# 3V3_LDO.net
KiCad netlist of a schematic drawn in Altium Designer
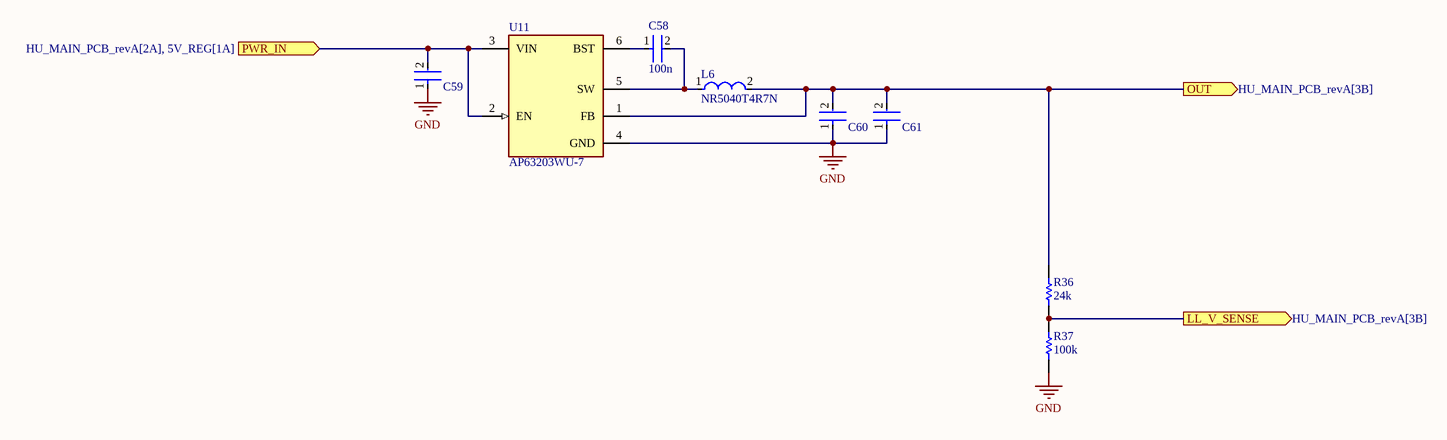
[diagram p0: 3V3_LDO.SchDoc]

(export (version "E")
  (design (tool "Eeschema 10.0.6"))
  (components
    (comp (ref "C58")
      (value "100n")
      (footprint "FP-0402-L_1_0_0_05-W_0_5-IPC_A")
      (description "LARGE PADS, 0402 CAP, CHANGE COMMENT TO MATCH REAL P/N")
      (libsource (lib "Space Concordia") (part "b4654b650e69147ec39a6b967a45e02"))
    )
    (comp (ref "C59")
      (value "GRM21BR61E226ME44L")
      (footprint "FP-GRM21B-0_2-e0_2_0_7-IPC_B")
      (description "Chip Multilayer Ceramic Capacitors for General Purpose, 0805, 22uF, X5R, 15%, 20%, 25V")
      (fields (field (name "TOLERANCE") "20%") (field (name "VOLTAGE") "25V"))
      (libsource (lib "Altium Content Vault") (part "b4654b650e69147ec39a6b967a45e02"))
    )
    (comp (ref "C60")
      (value "GRM21BR61E226ME44L")
      (footprint "FP-GRM21B-0_2-e0_2_0_7-IPC_B")
      (description "Chip Multilayer Ceramic Capacitors for General Purpose, 0805, 22uF, X5R, 15%, 20%, 25V")
      (fields (field (name "TOLERANCE") "20%") (field (name "VOLTAGE") "25V"))
      (libsource (lib "Altium Content Vault") (part "b4654b650e69147ec39a6b967a45e02"))
    )
    (comp (ref "C61")
      (value "GRM21BR61E226ME44L")
      (footprint "FP-GRM21B-0_2-e0_2_0_7-IPC_B")
      (description "Chip Multilayer Ceramic Capacitors for General Purpose, 0805, 22uF, X5R, 15%, 20%, 25V")
      (fields (field (name "TOLERANCE") "20%") (field (name "VOLTAGE") "25V"))
      (libsource (lib "Altium Content Vault") (part "b4654b650e69147ec39a6b967a45e02"))
    )
    (comp (ref "L6")
      (value "NR5040T4R7N")
      (footprint "FP-NR5040-H_4_1-MFG")
      (description "SMD Power Inductors 4.7uH ±30% 3.1A 37.7mΩ")
      (fields (field (name "TOLERANCE") "30%"))
      (libsource (lib "Altium Content Vault") (part "725321dda6339637d4d059423bc1c3c"))
    )
    (comp (ref "R36")
      (value "24k")
      (footprint "R0603B")
      (description "Resistor")
      (libsource (lib "Space Concordia") (part "Resistor"))
    )
    (comp (ref "R37")
      (value "100k")
      (footprint "R0603B")
      (description "Resistor")
      (libsource (lib "Space Concordia") (part "Resistor"))
    )
    (comp (ref "U11")
      (value "AP63203WU-7")
      (footprint "FP-TSOT26-MFG")
      (description "IC REG BUCK 3.3V 2A TSOT26")
      (fields
        (field (name "MANUFACTURER") "Diodes Inc.")
        (field (name "OCTOPART") "https://octopart.com/ap63203wu-7-diodes+inc.-98099550")
      )
      (libsource (lib "Altium Content Vault") (part "0e61c2974d7114b43f01ef96ae2e524"))
    )
  )
  (nets
    (net (code "1") (name "/LL_V_SENSE") (class "Default")
      (node (ref "R36") (pin "1") (pinfunction "1_1") (pintype "passive"))
      (node (ref "R37") (pin "2") (pinfunction "2_2") (pintype "passive"))
    )
    (net (code "2") (name "/OUT") (class "Default")
      (node (ref "C60") (pin "2") (pinfunction "2_2") (pintype "passive"))
      (node (ref "C61") (pin "2") (pinfunction "2_2") (pintype "passive"))
      (node (ref "L6") (pin "2") (pinfunction "2_2") (pintype "passive"))
      (node (ref "R36") (pin "2") (pinfunction "2_2") (pintype "passive"))
      (node (ref "U11") (pin "1") (pinfunction "FB_1") (pintype "passive"))
    )
    (net (code "3") (name "/PWR_IN") (class "Default")
      (node (ref "C59") (pin "2") (pinfunction "2_2") (pintype "passive"))
      (node (ref "U11") (pin "2") (pinfunction "EN_2") (pintype "input"))
      (node (ref "U11") (pin "3") (pinfunction "VIN_3") (pintype "power_in"))
    )
    (net (code "4") (name "GND") (class "Default")
      (node (ref "C59") (pin "1") (pinfunction "1_1") (pintype "passive"))
      (node (ref "C60") (pin "1") (pinfunction "1_1") (pintype "passive"))
      (node (ref "C61") (pin "1") (pinfunction "1_1") (pintype "passive"))
      (node (ref "R37") (pin "1") (pinfunction "1_1") (pintype "passive"))
      (node (ref "U11") (pin "4") (pinfunction "GND_4") (pintype "power_in"))
    )
    (net (code "5") (name "Net-(U11-BST)") (class "Default")
      (node (ref "C58") (pin "1") (pinfunction "1_1") (pintype "passive"))
      (node (ref "U11") (pin "6") (pinfunction "BST_6") (pintype "passive"))
    )
    (net (code "6") (name "Net-(U11-SW)") (class "Default")
      (node (ref "C58") (pin "2") (pinfunction "2_2") (pintype "passive"))
      (node (ref "L6") (pin "1") (pinfunction "1_1") (pintype "passive"))
      (node (ref "U11") (pin "5") (pinfunction "SW_5") (pintype "passive"))
    )
  )
)
